# MainCirctuit.net
KiCad netlist of a schematic drawn in EAGLE
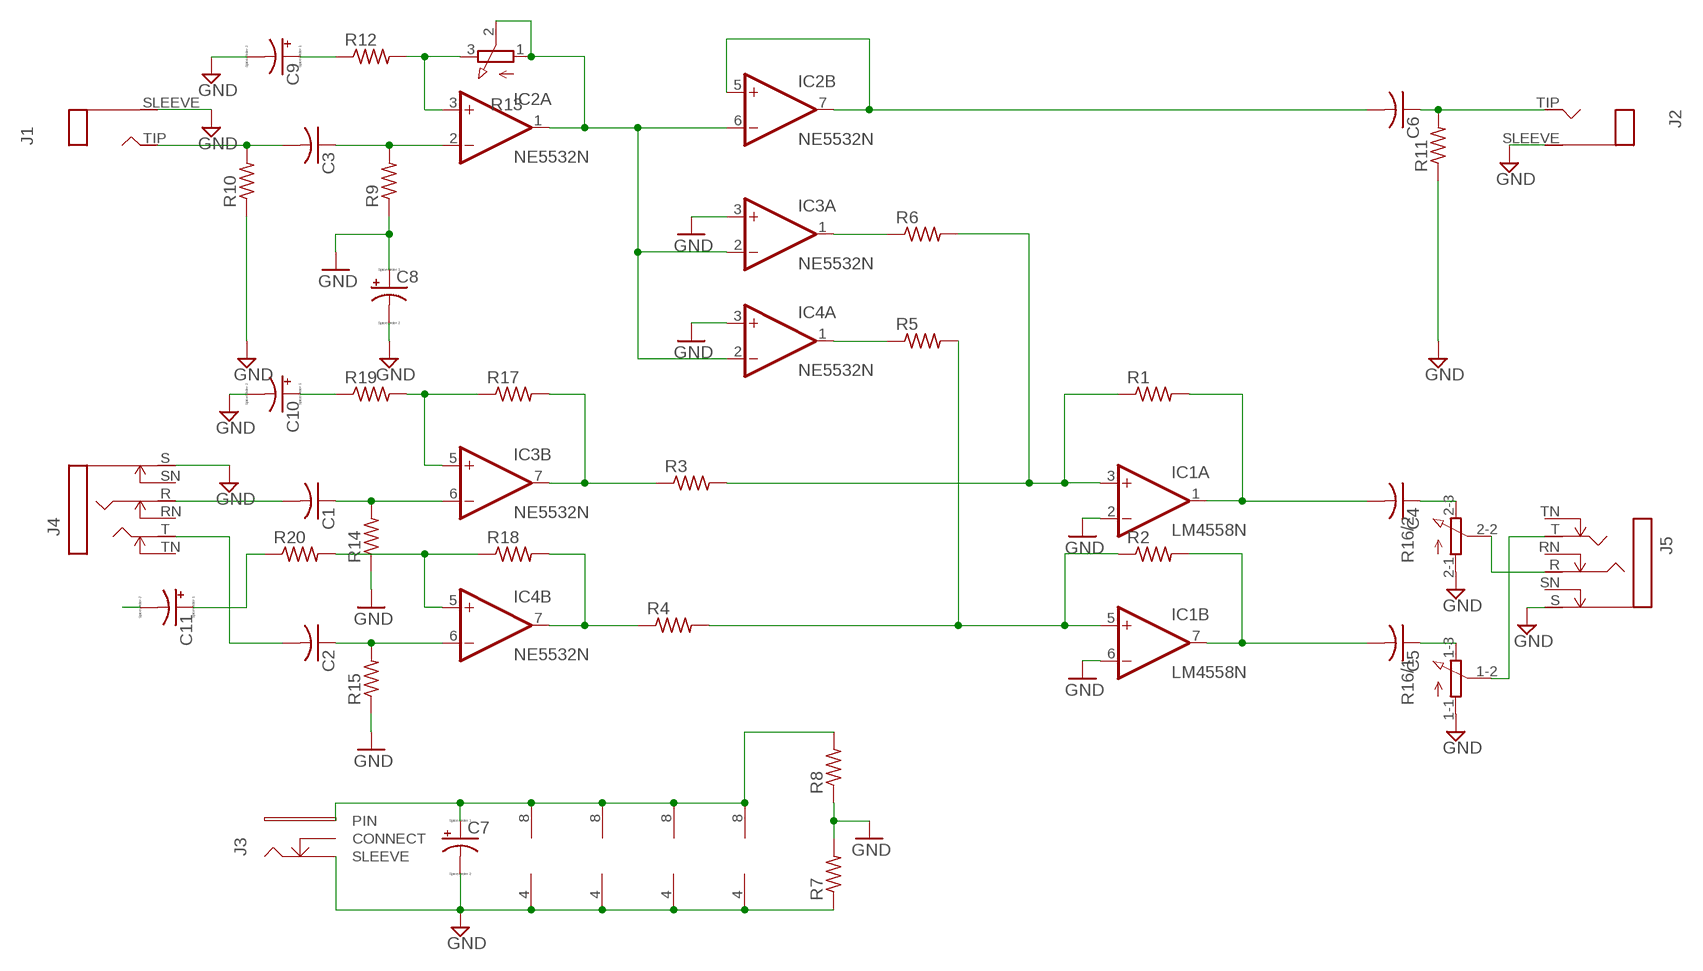
[diagram p0: schematic, sheet 1]

(export (version "E")
  (design (tool "Eeschema 10.0.6"))
  (components
    (comp (ref "C1")
      (value "C-US050-025X075")
      (footprint "eagle-import:C050-025X075")
      (libsource (lib "eagle-import") (part "C-US050-025X075"))
    )
    (comp (ref "C2")
      (value "C-US050-025X075")
      (footprint "eagle-import:C050-025X075")
      (libsource (lib "eagle-import") (part "C-US050-025X075"))
    )
    (comp (ref "C3")
      (value "C-US050-025X075")
      (footprint "eagle-import:C050-025X075")
      (libsource (lib "eagle-import") (part "C-US050-025X075"))
    )
    (comp (ref "C4")
      (value "C-US050-025X075")
      (footprint "eagle-import:C050-025X075")
      (libsource (lib "eagle-import") (part "C-US050-025X075"))
    )
    (comp (ref "C5")
      (value "C-US050-025X075")
      (footprint "eagle-import:C050-025X075")
      (libsource (lib "eagle-import") (part "C-US050-025X075"))
    )
    (comp (ref "C6")
      (value "C-US050-025X075")
      (footprint "eagle-import:C050-025X075")
      (libsource (lib "eagle-import") (part "C-US050-025X075"))
    )
    (comp (ref "C7")
      (value "CPOL-USE2,5-6E")
      (footprint "eagle-import:E2,5-6E")
      (libsource (lib "eagle-import") (part "CPOL-USE2,5-6E"))
    )
    (comp (ref "C8")
      (value "CPOL-USE2,5-6E")
      (footprint "eagle-import:E2,5-6E")
      (libsource (lib "eagle-import") (part "CPOL-USE2,5-6E"))
    )
    (comp (ref "C9")
      (value "CPOL-USE2,5-6E")
      (footprint "eagle-import:E2,5-6E")
      (libsource (lib "eagle-import") (part "CPOL-USE2,5-6E"))
    )
    (comp (ref "C10")
      (value "CPOL-USE2,5-6E")
      (footprint "eagle-import:E2,5-6E")
      (libsource (lib "eagle-import") (part "CPOL-USE2,5-6E"))
    )
    (comp (ref "C11")
      (value "CPOL-USE2,5-6E")
      (footprint "eagle-import:E2,5-6E")
      (libsource (lib "eagle-import") (part "CPOL-USE2,5-6E"))
    )
    (comp (ref "IC1")
      (value "LM4558N")
      (footprint "eagle-import:DIL08")
      (libsource (lib "eagle-import") (part "4558NLM"))
    )
    (comp (ref "IC2")
      (value "NE5532N")
      (footprint "eagle-import:DIL08")
      (libsource (lib "eagle-import") (part "NE5532N"))
    )
    (comp (ref "IC3")
      (value "NE5532N")
      (footprint "eagle-import:DIL08")
      (libsource (lib "eagle-import") (part "NE5532N"))
    )
    (comp (ref "IC4")
      (value "NE5532N")
      (footprint "eagle-import:DIL08")
      (libsource (lib "eagle-import") (part "NE5532N"))
    )
    (comp (ref "J1")
      (value "MONOA")
      (footprint "eagle-import:MONO_JACK_A")
      (libsource (lib "eagle-import") (part "MONOA"))
    )
    (comp (ref "J2")
      (value "MONOA")
      (footprint "eagle-import:MONO_JACK_A")
      (libsource (lib "eagle-import") (part "MONOA"))
    )
    (comp (ref "J3")
      (value "DC")
      (footprint "eagle-import:DC_POWER_JACK")
      (libsource (lib "eagle-import") (part "DC"))
    )
    (comp (ref "J4")
      (value "STEREOSW")
      (footprint "eagle-import:NMJ6HCD2")
      (libsource (lib "eagle-import") (part "STEREOSW"))
    )
    (comp (ref "J5")
      (value "STEREOSW")
      (footprint "eagle-import:NMJ6HCD2")
      (libsource (lib "eagle-import") (part "STEREOSW"))
    )
    (comp (ref "R1")
      (value "R-US_0204/7")
      (footprint "eagle-import:0204_7")
      (libsource (lib "eagle-import") (part "R-US_0204/7"))
    )
    (comp (ref "R2")
      (value "R-US_0204/7")
      (footprint "eagle-import:0204_7")
      (libsource (lib "eagle-import") (part "R-US_0204/7"))
    )
    (comp (ref "R3")
      (value "R-US_0204/7")
      (footprint "eagle-import:0204_7")
      (libsource (lib "eagle-import") (part "R-US_0204/7"))
    )
    (comp (ref "R4")
      (value "R-US_0204/7")
      (footprint "eagle-import:0204_7")
      (libsource (lib "eagle-import") (part "R-US_0204/7"))
    )
    (comp (ref "R5")
      (value "R-US_0204/7")
      (footprint "eagle-import:0204_7")
      (libsource (lib "eagle-import") (part "R-US_0204/7"))
    )
    (comp (ref "R6")
      (value "R-US_0204/7")
      (footprint "eagle-import:0204_7")
      (libsource (lib "eagle-import") (part "R-US_0204/7"))
    )
    (comp (ref "R7")
      (value "R-US_0204/7")
      (footprint "eagle-import:0204_7")
      (libsource (lib "eagle-import") (part "R-US_0204/7"))
    )
    (comp (ref "R8")
      (value "R-US_0204/7")
      (footprint "eagle-import:0204_7")
      (libsource (lib "eagle-import") (part "R-US_0204/7"))
    )
    (comp (ref "R9")
      (value "R-US_0204/7")
      (footprint "eagle-import:0204_7")
      (libsource (lib "eagle-import") (part "R-US_0204/7"))
    )
    (comp (ref "R10")
      (value "R-US_0204/7")
      (footprint "eagle-import:0204_7")
      (libsource (lib "eagle-import") (part "R-US_0204/7"))
    )
    (comp (ref "R11")
      (value "R-US_0204/7")
      (footprint "eagle-import:0204_7")
      (libsource (lib "eagle-import") (part "R-US_0204/7"))
    )
    (comp (ref "R12")
      (value "R-US_0204/7")
      (footprint "eagle-import:0204_7")
      (libsource (lib "eagle-import") (part "R-US_0204/7"))
    )
    (comp (ref "R13")
      (value "3RP/1610N")
      (footprint "eagle-import:3RP_1610N")
      (libsource (lib "eagle-import") (part "3RP/1610N"))
    )
    (comp (ref "R14")
      (value "R-US_0204/7")
      (footprint "eagle-import:0204_7")
      (libsource (lib "eagle-import") (part "R-US_0204/7"))
    )
    (comp (ref "R15")
      (value "R-US_0204/7")
      (footprint "eagle-import:0204_7")
      (libsource (lib "eagle-import") (part "R-US_0204/7"))
    )
    (comp (ref "R16")
      (value "3RP/1610G")
      (footprint "eagle-import:3RP_1610G")
      (libsource (lib "eagle-import") (part "3RP/1610G"))
    )
    (comp (ref "R17")
      (value "R-US_0204/7")
      (footprint "eagle-import:0204_7")
      (libsource (lib "eagle-import") (part "R-US_0204/7"))
    )
    (comp (ref "R18")
      (value "R-US_0204/7")
      (footprint "eagle-import:0204_7")
      (libsource (lib "eagle-import") (part "R-US_0204/7"))
    )
    (comp (ref "R19")
      (value "R-US_0204/7")
      (footprint "eagle-import:0204_7")
      (libsource (lib "eagle-import") (part "R-US_0204/7"))
    )
    (comp (ref "R20")
      (value "R-US_0204/7")
      (footprint "eagle-import:0204_7")
      (libsource (lib "eagle-import") (part "R-US_0204/7"))
    )
  )
  (nets
    (net (code "1") (name "GND") (class "Default")
      (node (ref "C10") (pin "-") (pinfunction "-_-") (pintype "passive"))
      (node (ref "C7") (pin "-") (pinfunction "-_-") (pintype "passive"))
      (node (ref "C8") (pin "+") (pinfunction "+_+") (pintype "passive"))
      (node (ref "C8") (pin "-") (pinfunction "-_-") (pintype "passive"))
      (node (ref "C9") (pin "-") (pinfunction "-_-") (pintype "passive"))
      (node (ref "IC1") (pin "2") (pinfunction "-IN_2") (pintype "input"))
      (node (ref "IC1") (pin "4") (pinfunction "V-_4") (pintype "power_in"))
      (node (ref "IC1") (pin "6") (pinfunction "-IN_6") (pintype "input"))
      (node (ref "IC2") (pin "4") (pinfunction "V-_4") (pintype "power_in"))
      (node (ref "IC3") (pin "3") (pinfunction "+IN_3") (pintype "input"))
      (node (ref "IC3") (pin "4") (pinfunction "V-_4") (pintype "power_in"))
      (node (ref "IC4") (pin "3") (pinfunction "+IN_3") (pintype "input"))
      (node (ref "IC4") (pin "4") (pinfunction "V-_4") (pintype "power_in"))
      (node (ref "J1") (pin "SLEEVE") (pinfunction "SLEEVE_SLEEVE") (pintype "passive"))
      (node (ref "J2") (pin "SLEEVE") (pinfunction "SLEEVE_SLEEVE") (pintype "passive"))
      (node (ref "J3") (pin "SLEEVE") (pinfunction "SLEEVE_SLEEVE") (pintype "passive"))
      (node (ref "J4") (pin "S") (pinfunction "S_S") (pintype "passive"))
      (node (ref "J5") (pin "S") (pinfunction "S_S") (pintype "passive"))
      (node (ref "R10") (pin "1") (pinfunction "1_1") (pintype "passive"))
      (node (ref "R11") (pin "1") (pinfunction "1_1") (pintype "passive"))
      (node (ref "R14") (pin "1") (pinfunction "1_1") (pintype "passive"))
      (node (ref "R15") (pin "1") (pinfunction "1_1") (pintype "passive"))
      (node (ref "R16") (pin "1-1") (pinfunction "A_1-1") (pintype "passive"))
      (node (ref "R16") (pin "2-1") (pinfunction "A_2-1") (pintype "passive"))
      (node (ref "R7") (pin "1") (pinfunction "1_1") (pintype "passive"))
      (node (ref "R7") (pin "2") (pinfunction "2_2") (pintype "passive"))
      (node (ref "R8") (pin "1") (pinfunction "1_1") (pintype "passive"))
      (node (ref "R9") (pin "1") (pinfunction "1_1") (pintype "passive"))
    )
    (net (code "2") (name "Net-(C1-Pad2)") (class "Default")
      (node (ref "C1") (pin "2") (pinfunction "2_2") (pintype "passive"))
      (node (ref "J4") (pin "R") (pinfunction "R_R") (pintype "passive"))
    )
    (net (code "3") (name "Net-(C2-Pad2)") (class "Default")
      (node (ref "C2") (pin "2") (pinfunction "2_2") (pintype "passive"))
      (node (ref "J4") (pin "T") (pinfunction "T_T") (pintype "passive"))
    )
    (net (code "4") (name "Net-(C3-Pad2)") (class "Default")
      (node (ref "C3") (pin "2") (pinfunction "2_2") (pintype "passive"))
      (node (ref "J1") (pin "TIP") (pinfunction "TIP_TIP") (pintype "passive"))
      (node (ref "R10") (pin "2") (pinfunction "2_2") (pintype "passive"))
    )
    (net (code "5") (name "Net-(C6-Pad1)") (class "Default")
      (node (ref "C6") (pin "1") (pinfunction "1_1") (pintype "passive"))
      (node (ref "J2") (pin "TIP") (pinfunction "TIP_TIP") (pintype "passive"))
      (node (ref "R11") (pin "2") (pinfunction "2_2") (pintype "passive"))
    )
    (net (code "6") (name "Net-(C9-Pad+)") (class "Default")
      (node (ref "C9") (pin "+") (pinfunction "+_+") (pintype "passive"))
      (node (ref "R12") (pin "1") (pinfunction "1_1") (pintype "passive"))
    )
    (net (code "7") (name "Net-(C10-Pad+)") (class "Default")
      (node (ref "C10") (pin "+") (pinfunction "+_+") (pintype "passive"))
      (node (ref "R19") (pin "1") (pinfunction "1_1") (pintype "passive"))
    )
    (net (code "8") (name "Net-(C11-Pad+)") (class "Default")
      (node (ref "C11") (pin "+") (pinfunction "+_+") (pintype "passive"))
      (node (ref "R20") (pin "1") (pinfunction "1_1") (pintype "passive"))
    )
    (net (code "9") (name "Net-(IC1A-+IN)") (class "Default")
      (node (ref "IC1") (pin "3") (pinfunction "+IN_3") (pintype "input"))
      (node (ref "R1") (pin "1") (pinfunction "1_1") (pintype "passive"))
      (node (ref "R3") (pin "2") (pinfunction "2_2") (pintype "passive"))
      (node (ref "R6") (pin "2") (pinfunction "2_2") (pintype "passive"))
    )
    (net (code "10") (name "Net-(IC1A-OUT)") (class "Default")
      (node (ref "C4") (pin "2") (pinfunction "2_2") (pintype "passive"))
      (node (ref "IC1") (pin "1") (pinfunction "OUT_1") (pintype "output"))
      (node (ref "R1") (pin "2") (pinfunction "2_2") (pintype "passive"))
    )
    (net (code "11") (name "Net-(IC1B-+IN)") (class "Default")
      (node (ref "IC1") (pin "5") (pinfunction "+IN_5") (pintype "input"))
      (node (ref "R2") (pin "1") (pinfunction "1_1") (pintype "passive"))
      (node (ref "R4") (pin "2") (pinfunction "2_2") (pintype "passive"))
      (node (ref "R5") (pin "2") (pinfunction "2_2") (pintype "passive"))
    )
    (net (code "12") (name "Net-(IC1B-OUT)") (class "Default")
      (node (ref "C5") (pin "2") (pinfunction "2_2") (pintype "passive"))
      (node (ref "IC1") (pin "7") (pinfunction "OUT_7") (pintype "output"))
      (node (ref "R2") (pin "2") (pinfunction "2_2") (pintype "passive"))
    )
    (net (code "13") (name "Net-(IC1C-V+)") (class "Default")
      (node (ref "C7") (pin "+") (pinfunction "+_+") (pintype "passive"))
      (node (ref "IC1") (pin "8") (pinfunction "V+_8") (pintype "power_in"))
      (node (ref "IC2") (pin "8") (pinfunction "V+_8") (pintype "power_in"))
      (node (ref "IC3") (pin "8") (pinfunction "V+_8") (pintype "power_in"))
      (node (ref "IC4") (pin "8") (pinfunction "V+_8") (pintype "power_in"))
      (node (ref "J3") (pin "PIN") (pinfunction "PIN_PIN") (pintype "passive"))
      (node (ref "R8") (pin "2") (pinfunction "2_2") (pintype "passive"))
    )
    (net (code "14") (name "Net-(IC2A-+IN)") (class "Default")
      (node (ref "IC2") (pin "3") (pinfunction "+IN_3") (pintype "input"))
      (node (ref "R12") (pin "2") (pinfunction "2_2") (pintype "passive"))
      (node (ref "R13") (pin "3") (pinfunction "E_3") (pintype "passive"))
    )
    (net (code "15") (name "Net-(IC2A--IN)") (class "Default")
      (node (ref "C3") (pin "1") (pinfunction "1_1") (pintype "passive"))
      (node (ref "IC2") (pin "2") (pinfunction "-IN_2") (pintype "input"))
      (node (ref "R9") (pin "2") (pinfunction "2_2") (pintype "passive"))
    )
    (net (code "16") (name "Net-(IC2A-OUT)") (class "Default")
      (node (ref "IC2") (pin "1") (pinfunction "OUT_1") (pintype "output"))
      (node (ref "IC2") (pin "6") (pinfunction "-IN_6") (pintype "input"))
      (node (ref "IC3") (pin "2") (pinfunction "-IN_2") (pintype "input"))
      (node (ref "IC4") (pin "2") (pinfunction "-IN_2") (pintype "input"))
      (node (ref "R13") (pin "1") (pinfunction "A_1") (pintype "passive"))
      (node (ref "R13") (pin "2") (pinfunction "S_2") (pintype "passive"))
    )
    (net (code "17") (name "Net-(IC2B-+IN)") (class "Default")
      (node (ref "C6") (pin "2") (pinfunction "2_2") (pintype "passive"))
      (node (ref "IC2") (pin "5") (pinfunction "+IN_5") (pintype "input"))
      (node (ref "IC2") (pin "7") (pinfunction "OUT_7") (pintype "output"))
    )
    (net (code "18") (name "Net-(IC3A-OUT)") (class "Default")
      (node (ref "IC3") (pin "1") (pinfunction "OUT_1") (pintype "output"))
      (node (ref "R6") (pin "1") (pinfunction "1_1") (pintype "passive"))
    )
    (net (code "19") (name "Net-(IC3B-+IN)") (class "Default")
      (node (ref "IC3") (pin "5") (pinfunction "+IN_5") (pintype "input"))
      (node (ref "R17") (pin "1") (pinfunction "1_1") (pintype "passive"))
      (node (ref "R19") (pin "2") (pinfunction "2_2") (pintype "passive"))
    )
    (net (code "20") (name "Net-(IC3B--IN)") (class "Default")
      (node (ref "C1") (pin "1") (pinfunction "1_1") (pintype "passive"))
      (node (ref "IC3") (pin "6") (pinfunction "-IN_6") (pintype "input"))
      (node (ref "R14") (pin "2") (pinfunction "2_2") (pintype "passive"))
    )
    (net (code "21") (name "Net-(IC3B-OUT)") (class "Default")
      (node (ref "IC3") (pin "7") (pinfunction "OUT_7") (pintype "output"))
      (node (ref "R17") (pin "2") (pinfunction "2_2") (pintype "passive"))
      (node (ref "R3") (pin "1") (pinfunction "1_1") (pintype "passive"))
    )
    (net (code "22") (name "Net-(IC4A-OUT)") (class "Default")
      (node (ref "IC4") (pin "1") (pinfunction "OUT_1") (pintype "output"))
      (node (ref "R5") (pin "1") (pinfunction "1_1") (pintype "passive"))
    )
    (net (code "23") (name "Net-(IC4B-+IN)") (class "Default")
      (node (ref "IC4") (pin "5") (pinfunction "+IN_5") (pintype "input"))
      (node (ref "R18") (pin "1") (pinfunction "1_1") (pintype "passive"))
      (node (ref "R20") (pin "2") (pinfunction "2_2") (pintype "passive"))
    )
    (net (code "24") (name "Net-(IC4B--IN)") (class "Default")
      (node (ref "C2") (pin "1") (pinfunction "1_1") (pintype "passive"))
      (node (ref "IC4") (pin "6") (pinfunction "-IN_6") (pintype "input"))
      (node (ref "R15") (pin "2") (pinfunction "2_2") (pintype "passive"))
    )
    (net (code "25") (name "Net-(IC4B-OUT)") (class "Default")
      (node (ref "IC4") (pin "7") (pinfunction "OUT_7") (pintype "output"))
      (node (ref "R18") (pin "2") (pinfunction "2_2") (pintype "passive"))
      (node (ref "R4") (pin "1") (pinfunction "1_1") (pintype "passive"))
    )
    (net (code "26") (name "Net-(R16A-E)") (class "Default")
      (node (ref "C5") (pin "1") (pinfunction "1_1") (pintype "passive"))
      (node (ref "R16") (pin "1-3") (pinfunction "E_1-3") (pintype "passive"))
    )
    (net (code "27") (name "Net-(R16A-S)") (class "Default")
      (node (ref "J5") (pin "T") (pinfunction "T_T") (pintype "passive"))
      (node (ref "R16") (pin "1-2") (pinfunction "S_1-2") (pintype "passive"))
    )
    (net (code "28") (name "Net-(R16B-E)") (class "Default")
      (node (ref "C4") (pin "1") (pinfunction "1_1") (pintype "passive"))
      (node (ref "R16") (pin "2-3") (pinfunction "E_2-3") (pintype "passive"))
    )
    (net (code "29") (name "Net-(R16B-S)") (class "Default")
      (node (ref "J5") (pin "R") (pinfunction "R_R") (pintype "passive"))
      (node (ref "R16") (pin "2-2") (pinfunction "S_2-2") (pintype "passive"))
    )
    (net (code "30") (name "unconnected-(C11-Pad-)") (class "Default")
      (node (ref "C11") (pin "-") (pinfunction "-_-") (pintype "passive"))
    )
    (net (code "31") (name "unconnected-(J3-CONNECT-PadCLOSE)") (class "Default")
      (node (ref "J3") (pin "CLOSE") (pinfunction "CONNECT_CLOSE") (pintype "passive"))
    )
    (net (code "32") (name "unconnected-(J4-PadRN)") (class "Default")
      (node (ref "J4") (pin "RN") (pinfunction "RN_RN") (pintype "passive"))
    )
    (net (code "33") (name "unconnected-(J4-PadSN)") (class "Default")
      (node (ref "J4") (pin "SN") (pinfunction "SN_SN") (pintype "passive"))
    )
    (net (code "34") (name "unconnected-(J4-PadTN)") (class "Default")
      (node (ref "J4") (pin "TN") (pinfunction "TN_TN") (pintype "passive"))
    )
    (net (code "35") (name "unconnected-(J5-PadRN)") (class "Default")
      (node (ref "J5") (pin "RN") (pinfunction "RN_RN") (pintype "passive"))
    )
    (net (code "36") (name "unconnected-(J5-PadSN)") (class "Default")
      (node (ref "J5") (pin "SN") (pinfunction "SN_SN") (pintype "passive"))
    )
    (net (code "37") (name "unconnected-(J5-PadTN)") (class "Default")
      (node (ref "J5") (pin "TN") (pinfunction "TN_TN") (pintype "passive"))
    )
  )
)
